# DistanceSensor.net
KiCad netlist of a schematic drawn in Altium Designer
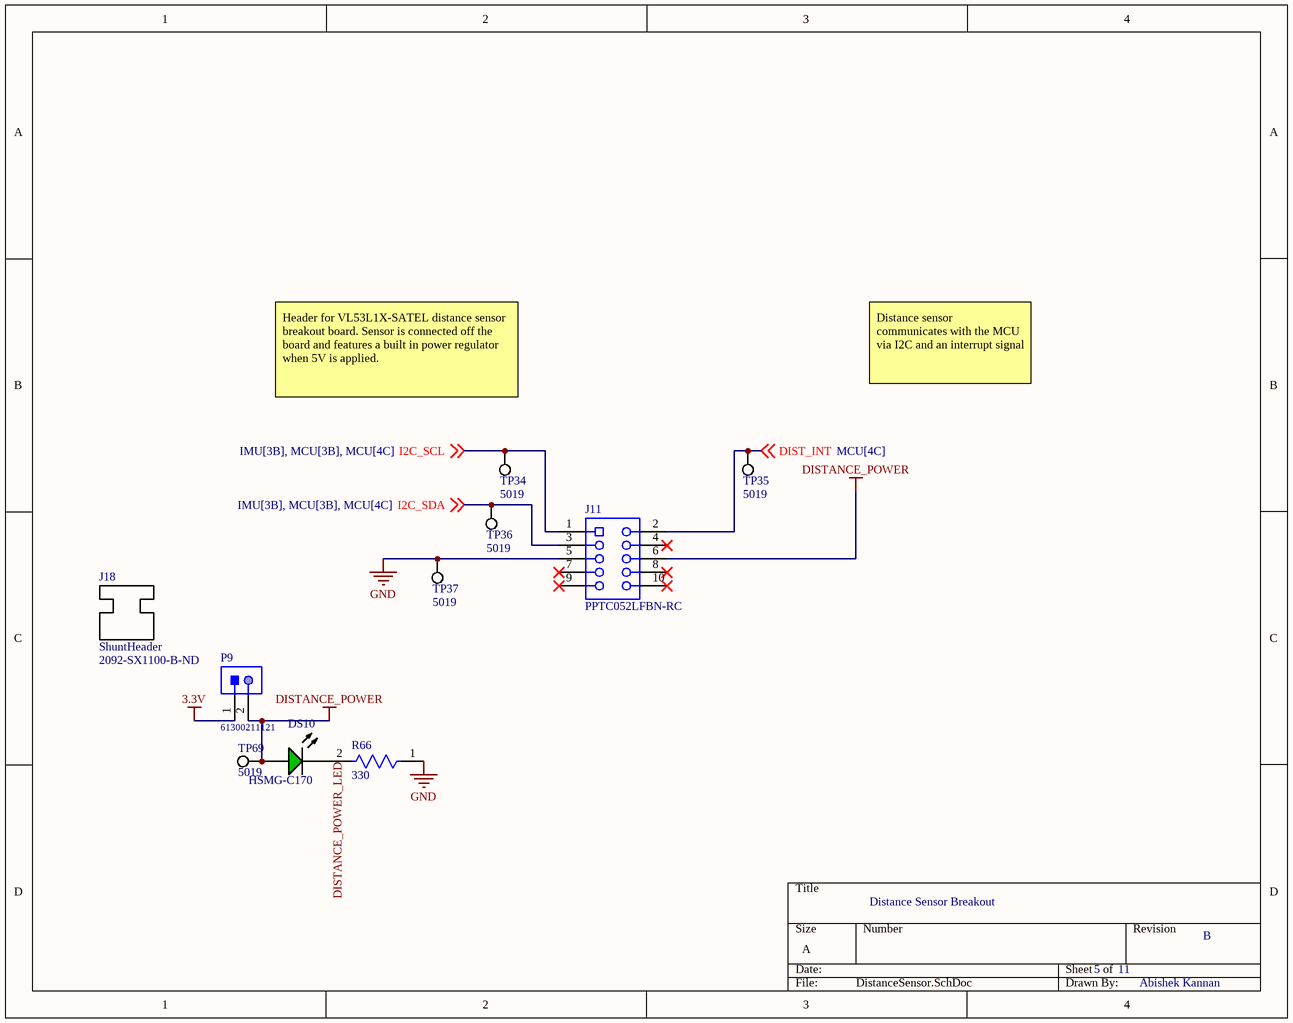
[diagram p0: DistanceSensor.SchDoc]

(export (version "E")
  (design (tool "Eeschema 10.0.6"))
  (components
    (comp (ref "DS10")
      (value "HSMG-C170")
      (footprint "AVAG-HSMX-C170_V")
      (description "Chip LED, Green, 2.2 V, -40 to 85 degC, 2-Pin SMD, Pb-Free, Tape and Reel")
      (fields (field (name "MANUFACTURER") "Avago"))
      (libsource (lib "Altium Content Vault") (part "LED_GREEN_A1K2-2"))
    )
    (comp (ref "J11")
      (value "PPTC052LFBN-RC")
      (footprint "SLIN-PPTC052LFBN-RC_V")
      (fields (field (name "MANUFACTURER") "Sullins"))
      (libsource (lib "Altium Content Vault") (part "CN-2P-F-R10"))
    )
    (comp (ref "J18")
      (value "ShuntHeader")
      (description "Conn Mini Shunt 2 POS 2.54mm Black Cable Mount")
      (fields
        (field (name "MANUFACTURER") "Kycon")
        (field (name "MANUFACTURER PART NUMBER") "SX1100-B")
        (field (name "SUPPLIER PART NUMBER 1") "2092-SX1100-B-ND")
      )
      (libsource (lib "CustomSchematics") (part "ShuntHeader"))
    )
    (comp (ref "P9")
      (value "61300211121")
      (footprint "61300211121")
      (description "THT Vertical Pin Header WR-PHD, Pitch 2.54 mm, Single Row, 2 pins")
      (fields (field (name "MANUFACTURER") "Wurth Elektronik") (field (name "PUBLISHER") "WurthElektronik"))
      (libsource (lib "Altium Content Vault") (part "WE-CN-1P-M-R2"))
    )
    (comp (ref "R66")
      (value "330")
      (footprint "FP-CRCW0805-e3-MFG")
      (description "RES Thick Film, 330Ω, 1%, 0.125W, 100ppm/°C, 0805")
      (fields (field (name "TOLERANCE") "1%") (field (name "MANUFACTURER") "Vishay"))
      (libsource (lib "Altium Content Vault") (part "1029c3af85768c4190bb7ad29bc67b5"))
    )
    (comp (ref "TP34")
      (value "5019")
      (footprint "KSTN-5019_V")
      (description "Test Point, 1 Position SMD, RoHS, Tape and Reel")
      (fields (field (name "MANUFACTURER") "Keystone Electronics"))
      (libsource (lib "Altium Content Vault") (part "TESTPOINT_WHITE"))
    )
    (comp (ref "TP35")
      (value "5019")
      (footprint "KSTN-5019_V")
      (description "Test Point, 1 Position SMD, RoHS, Tape and Reel")
      (fields (field (name "MANUFACTURER") "Keystone Electronics"))
      (libsource (lib "Altium Content Vault") (part "TESTPOINT_WHITE"))
    )
    (comp (ref "TP36")
      (value "5019")
      (footprint "KSTN-5019_V")
      (description "Test Point, 1 Position SMD, RoHS, Tape and Reel")
      (fields (field (name "MANUFACTURER") "Keystone Electronics"))
      (libsource (lib "Altium Content Vault") (part "TESTPOINT_WHITE"))
    )
    (comp (ref "TP37")
      (value "5019")
      (footprint "KSTN-5019_V")
      (description "Test Point, 1 Position SMD, RoHS, Tape and Reel")
      (fields (field (name "MANUFACTURER") "Keystone Electronics"))
      (libsource (lib "Altium Content Vault") (part "TESTPOINT_WHITE"))
    )
    (comp (ref "TP69")
      (value "5019")
      (footprint "KSTN-5019_V")
      (description "Test Point, 1 Position SMD, RoHS, Tape and Reel")
      (fields (field (name "MANUFACTURER") "Keystone Electronics"))
      (libsource (lib "Altium Content Vault") (part "TESTPOINT_WHITE"))
    )
  )
  (nets
    (net (code "1") (name "/DISTANCE_POWER_LED") (class "Default")
      (node (ref "DS10") (pin "2") (pinfunction "K_2") (pintype "passive"))
      (node (ref "R66") (pin "2") (pinfunction "2_2") (pintype "passive"))
    )
    (net (code "2") (name "3.3V") (class "Default")
      (node (ref "P9") (pin "1") (pinfunction "1_1") (pintype "passive"))
    )
    (net (code "3") (name "DISTANCE_POWER") (class "Default")
      (node (ref "DS10") (pin "1") (pinfunction "A_1") (pintype "passive"))
      (node (ref "J11") (pin "6") (pinfunction "6_6") (pintype "passive"))
      (node (ref "P9") (pin "2") (pinfunction "2_2") (pintype "passive"))
      (node (ref "TP69") (pin "1") (pinfunction "1_1") (pintype "passive"))
    )
    (net (code "4") (name "DIST_INT") (class "Default")
      (node (ref "J11") (pin "2") (pinfunction "2_2") (pintype "passive"))
      (node (ref "TP35") (pin "1") (pinfunction "1_1") (pintype "passive"))
    )
    (net (code "5") (name "GND") (class "Default")
      (node (ref "J11") (pin "5") (pinfunction "5_5") (pintype "passive"))
      (node (ref "R66") (pin "1") (pinfunction "1_1") (pintype "passive"))
      (node (ref "TP37") (pin "1") (pinfunction "1_1") (pintype "passive"))
    )
    (net (code "6") (name "I2C_SCL") (class "Default")
      (node (ref "J11") (pin "1") (pinfunction "1_1") (pintype "passive"))
      (node (ref "TP34") (pin "1") (pinfunction "1_1") (pintype "passive"))
    )
    (net (code "7") (name "I2C_SDA") (class "Default")
      (node (ref "J11") (pin "3") (pinfunction "3_3") (pintype "passive"))
      (node (ref "TP36") (pin "1") (pinfunction "1_1") (pintype "passive"))
    )
    (net (code "8") (name "unconnected-(J11-Pad4)") (class "Default")
      (node (ref "J11") (pin "4") (pinfunction "4_4") (pintype "passive+no_connect"))
    )
    (net (code "9") (name "unconnected-(J11-Pad7)") (class "Default")
      (node (ref "J11") (pin "7") (pinfunction "7_7") (pintype "passive+no_connect"))
    )
    (net (code "10") (name "unconnected-(J11-Pad8)") (class "Default")
      (node (ref "J11") (pin "8") (pinfunction "8_8") (pintype "passive+no_connect"))
    )
    (net (code "11") (name "unconnected-(J11-Pad9)") (class "Default")
      (node (ref "J11") (pin "9") (pinfunction "9_9") (pintype "passive+no_connect"))
    )
    (net (code "12") (name "unconnected-(J11-Pad10)") (class "Default")
      (node (ref "J11") (pin "10") (pinfunction "10_10") (pintype "passive+no_connect"))
    )
  )
)
